# working.net
KiCad netlist of a schematic drawn in EAGLE
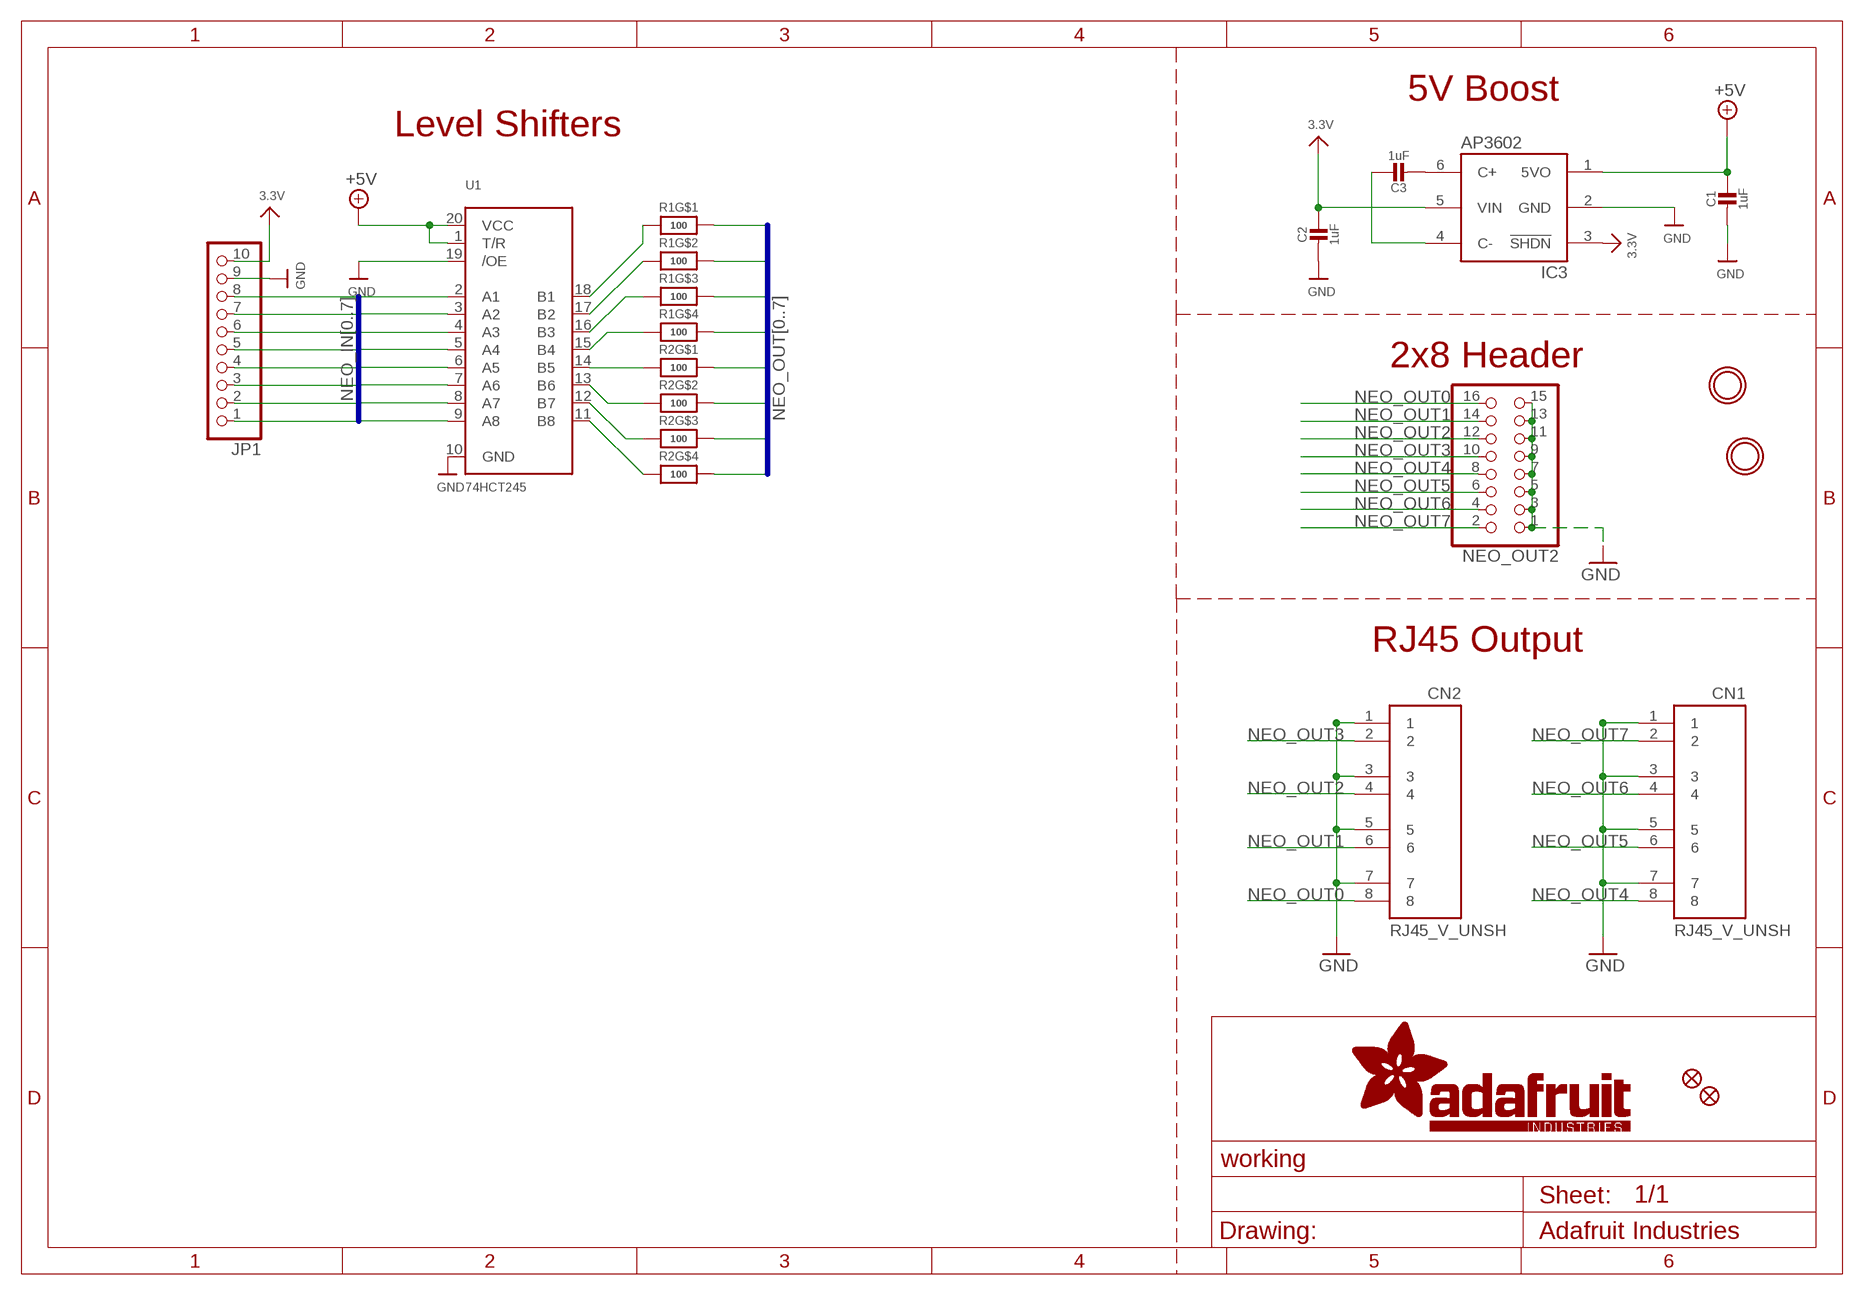
[diagram p0: schematic, sheet 1]

(export (version "E")
  (design (tool "Eeschema 10.0.6"))
  (components
    (comp (ref "C1")
      (value "1uF")
      (footprint "eagle-import:0603-NO")
      (libsource (lib "eagle-import") (part "CAP_CERAMIC0603_NO"))
    )
    (comp (ref "C2")
      (value "1uF")
      (footprint "eagle-import:0603-NO")
      (libsource (lib "eagle-import") (part "CAP_CERAMIC0603_NO"))
    )
    (comp (ref "C3")
      (value "1uF")
      (footprint "eagle-import:0603-NO")
      (libsource (lib "eagle-import") (part "CAP_CERAMIC0603_NO"))
    )
    (comp (ref "CN1")
      (value "RJ45_V_UNSH")
      (footprint "eagle-import:RJ45_VERTICAL_UNSHIELDED")
      (libsource (lib "eagle-import") (part "RJ45_V_UNSH"))
    )
    (comp (ref "CN2")
      (value "RJ45_V_UNSH")
      (footprint "eagle-import:RJ45_VERTICAL_UNSHIELDED")
      (libsource (lib "eagle-import") (part "RJ45_V_UNSH"))
    )
    (comp (ref "FID1")
      (value "FIDUCIAL_1MM")
      (footprint "eagle-import:FIDUCIAL_1MM")
      (libsource (lib "eagle-import") (part "FIDUCIAL_1MM"))
    )
    (comp (ref "FID2")
      (value "FIDUCIAL_1MM")
      (footprint "eagle-import:FIDUCIAL_1MM")
      (libsource (lib "eagle-import") (part "FIDUCIAL_1MM"))
    )
    (comp (ref "IC3")
      (value "AP3602")
      (footprint "eagle-import:SOT23-6")
      (libsource (lib "eagle-import") (part "AP3602"))
    )
    (comp (ref "JP1")
      (value "HEADER-1X1070MIL")
      (footprint "eagle-import:1X10_ROUND70")
      (libsource (lib "eagle-import") (part "HEADER-1X1070MIL"))
    )
    (comp (ref "NEO_OUT2")
      (value "HEADER-2X8")
      (footprint "eagle-import:2X08")
      (libsource (lib "eagle-import") (part "HEADER-2X8"))
    )
    (comp (ref "R1")
      (value "100")
      (footprint "eagle-import:RESPACK_4X0603")
      (libsource (lib "eagle-import") (part "RESISTOR_4PACK"))
    )
    (comp (ref "R2")
      (value "100")
      (footprint "eagle-import:RESPACK_4X0603")
      (libsource (lib "eagle-import") (part "RESISTOR_4PACK"))
    )
    (comp (ref "U$3")
      (value "MOUNTINGHOLE2.5")
      (footprint "eagle-import:MOUNTINGHOLE_2.5_PLATED")
      (libsource (lib "eagle-import") (part "MOUNTINGHOLE2.5"))
    )
    (comp (ref "U$7")
      (value "MOUNTINGHOLE2.5")
      (footprint "eagle-import:MOUNTINGHOLE_2.5_PLATED")
      (libsource (lib "eagle-import") (part "MOUNTINGHOLE2.5"))
    )
    (comp (ref "U1")
      (value "74HCT245")
      (footprint "eagle-import:TSSOP20")
      (libsource (lib "eagle-import") (part "74LCX245"))
    )
  )
  (nets
    (net (code "1") (name "+5V") (class "Default")
      (node (ref "C1") (pin "1") (pinfunction "1_1") (pintype "passive"))
      (node (ref "IC3") (pin "1") (pinfunction "5VO_1") (pintype "power_in"))
      (node (ref "U1") (pin "1") (pinfunction "T/R_1") (pintype "bidirectional"))
      (node (ref "U1") (pin "20") (pinfunction "VCC_20") (pintype "bidirectional"))
    )
    (net (code "2") (name "/NEO_IN0") (class "Default")
      (node (ref "JP1") (pin "8") (pinfunction "8_8") (pintype "passive"))
      (node (ref "U1") (pin "2") (pinfunction "A1_2") (pintype "bidirectional"))
    )
    (net (code "3") (name "/NEO_IN1") (class "Default")
      (node (ref "JP1") (pin "7") (pinfunction "7_7") (pintype "passive"))
      (node (ref "U1") (pin "3") (pinfunction "A2_3") (pintype "bidirectional"))
    )
    (net (code "4") (name "/NEO_IN2") (class "Default")
      (node (ref "JP1") (pin "6") (pinfunction "6_6") (pintype "passive"))
      (node (ref "U1") (pin "4") (pinfunction "A3_4") (pintype "bidirectional"))
    )
    (net (code "5") (name "/NEO_IN3") (class "Default")
      (node (ref "JP1") (pin "5") (pinfunction "5_5") (pintype "passive"))
      (node (ref "U1") (pin "5") (pinfunction "A4_5") (pintype "bidirectional"))
    )
    (net (code "6") (name "/NEO_IN4") (class "Default")
      (node (ref "JP1") (pin "4") (pinfunction "4_4") (pintype "passive"))
      (node (ref "U1") (pin "6") (pinfunction "A5_6") (pintype "bidirectional"))
    )
    (net (code "7") (name "/NEO_IN5") (class "Default")
      (node (ref "JP1") (pin "3") (pinfunction "3_3") (pintype "passive"))
      (node (ref "U1") (pin "7") (pinfunction "A6_7") (pintype "bidirectional"))
    )
    (net (code "8") (name "/NEO_IN6") (class "Default")
      (node (ref "JP1") (pin "2") (pinfunction "2_2") (pintype "passive"))
      (node (ref "U1") (pin "8") (pinfunction "A7_8") (pintype "bidirectional"))
    )
    (net (code "9") (name "/NEO_IN7") (class "Default")
      (node (ref "JP1") (pin "1") (pinfunction "1_1") (pintype "passive"))
      (node (ref "U1") (pin "9") (pinfunction "A8_9") (pintype "bidirectional"))
    )
    (net (code "10") (name "/NEO_OUT0") (class "Default")
      (node (ref "CN2") (pin "8") (pinfunction "8_8") (pintype "bidirectional"))
      (node (ref "NEO_OUT2") (pin "16") (pinfunction "16_16") (pintype "passive"))
      (node (ref "R1") (pin "8") (pinfunction "2_8") (pintype "passive"))
    )
    (net (code "11") (name "/NEO_OUT1") (class "Default")
      (node (ref "CN2") (pin "6") (pinfunction "6_6") (pintype "bidirectional"))
      (node (ref "NEO_OUT2") (pin "14") (pinfunction "14_14") (pintype "passive"))
      (node (ref "R1") (pin "7") (pinfunction "2_7") (pintype "passive"))
    )
    (net (code "12") (name "/NEO_OUT2") (class "Default")
      (node (ref "CN2") (pin "4") (pinfunction "4_4") (pintype "bidirectional"))
      (node (ref "NEO_OUT2") (pin "12") (pinfunction "12_12") (pintype "passive"))
      (node (ref "R1") (pin "6") (pinfunction "2_6") (pintype "passive"))
    )
    (net (code "13") (name "/NEO_OUT3") (class "Default")
      (node (ref "CN2") (pin "2") (pinfunction "2_2") (pintype "bidirectional"))
      (node (ref "NEO_OUT2") (pin "10") (pinfunction "10_10") (pintype "passive"))
      (node (ref "R1") (pin "5") (pinfunction "2_5") (pintype "passive"))
    )
    (net (code "14") (name "/NEO_OUT4") (class "Default")
      (node (ref "CN1") (pin "8") (pinfunction "8_8") (pintype "bidirectional"))
      (node (ref "NEO_OUT2") (pin "8") (pinfunction "8_8") (pintype "passive"))
      (node (ref "R2") (pin "8") (pinfunction "2_8") (pintype "passive"))
    )
    (net (code "15") (name "/NEO_OUT5") (class "Default")
      (node (ref "CN1") (pin "6") (pinfunction "6_6") (pintype "bidirectional"))
      (node (ref "NEO_OUT2") (pin "6") (pinfunction "6_6") (pintype "passive"))
      (node (ref "R2") (pin "7") (pinfunction "2_7") (pintype "passive"))
    )
    (net (code "16") (name "/NEO_OUT6") (class "Default")
      (node (ref "CN1") (pin "4") (pinfunction "4_4") (pintype "bidirectional"))
      (node (ref "NEO_OUT2") (pin "4") (pinfunction "4_4") (pintype "passive"))
      (node (ref "R2") (pin "6") (pinfunction "2_6") (pintype "passive"))
    )
    (net (code "17") (name "/NEO_OUT7") (class "Default")
      (node (ref "CN1") (pin "2") (pinfunction "2_2") (pintype "bidirectional"))
      (node (ref "NEO_OUT2") (pin "2") (pinfunction "2_2") (pintype "passive"))
      (node (ref "R2") (pin "5") (pinfunction "2_5") (pintype "passive"))
    )
    (net (code "19") (name "3.3V") (class "Default")
      (node (ref "C2") (pin "1") (pinfunction "1_1") (pintype "passive"))
      (node (ref "IC3") (pin "3") (pinfunction "~{SHDN}_3") (pintype "input"))
      (node (ref "IC3") (pin "5") (pinfunction "VIN_5") (pintype "power_in"))
      (node (ref "JP1") (pin "10") (pinfunction "10_10") (pintype "passive"))
    )
    (net (code "20") (name "GND") (class "Default")
      (node (ref "C1") (pin "2") (pinfunction "2_2") (pintype "passive"))
      (node (ref "C2") (pin "2") (pinfunction "2_2") (pintype "passive"))
      (node (ref "CN1") (pin "1") (pinfunction "1_1") (pintype "bidirectional"))
      (node (ref "CN1") (pin "3") (pinfunction "3_3") (pintype "bidirectional"))
      (node (ref "CN1") (pin "5") (pinfunction "5_5") (pintype "bidirectional"))
      (node (ref "CN1") (pin "7") (pinfunction "7_7") (pintype "bidirectional"))
      (node (ref "CN2") (pin "1") (pinfunction "1_1") (pintype "bidirectional"))
      (node (ref "CN2") (pin "3") (pinfunction "3_3") (pintype "bidirectional"))
      (node (ref "CN2") (pin "5") (pinfunction "5_5") (pintype "bidirectional"))
      (node (ref "CN2") (pin "7") (pinfunction "7_7") (pintype "bidirectional"))
      (node (ref "IC3") (pin "2") (pinfunction "GND_2") (pintype "power_in"))
      (node (ref "JP1") (pin "9") (pinfunction "9_9") (pintype "passive"))
      (node (ref "NEO_OUT2") (pin "1") (pinfunction "1_1") (pintype "passive"))
      (node (ref "NEO_OUT2") (pin "11") (pinfunction "11_11") (pintype "passive"))
      (node (ref "NEO_OUT2") (pin "13") (pinfunction "13_13") (pintype "passive"))
      (node (ref "NEO_OUT2") (pin "15") (pinfunction "15_15") (pintype "passive"))
      (node (ref "NEO_OUT2") (pin "3") (pinfunction "3_3") (pintype "passive"))
      (node (ref "NEO_OUT2") (pin "5") (pinfunction "5_5") (pintype "passive"))
      (node (ref "NEO_OUT2") (pin "7") (pinfunction "7_7") (pintype "passive"))
      (node (ref "NEO_OUT2") (pin "9") (pinfunction "9_9") (pintype "passive"))
      (node (ref "U1") (pin "10") (pinfunction "GND_10") (pintype "bidirectional"))
      (node (ref "U1") (pin "19") (pinfunction "/OE_19") (pintype "bidirectional"))
    )
    (net (code "21") (name "Net-(IC3-C+)") (class "Default")
      (node (ref "C3") (pin "2") (pinfunction "2_2") (pintype "passive"))
      (node (ref "IC3") (pin "6") (pinfunction "C+_6") (pintype "bidirectional"))
    )
    (net (code "22") (name "Net-(IC3-C-)") (class "Default")
      (node (ref "C3") (pin "1") (pinfunction "1_1") (pintype "passive"))
      (node (ref "IC3") (pin "4") (pinfunction "C-_4") (pintype "bidirectional"))
    )
    (net (code "23") (name "Net-(R1B-1)") (class "Default")
      (node (ref "R1") (pin "2") (pinfunction "1_2") (pintype "passive"))
      (node (ref "U1") (pin "17") (pinfunction "B2_17") (pintype "bidirectional"))
    )
    (net (code "24") (name "Net-(R1C-1)") (class "Default")
      (node (ref "R1") (pin "3") (pinfunction "1_3") (pintype "passive"))
      (node (ref "U1") (pin "16") (pinfunction "B3_16") (pintype "bidirectional"))
    )
    (net (code "25") (name "Net-(R1D-1)") (class "Default")
      (node (ref "R1") (pin "4") (pinfunction "1_4") (pintype "passive"))
      (node (ref "U1") (pin "15") (pinfunction "B4_15") (pintype "bidirectional"))
    )
    (net (code "26") (name "Net-(R2B-1)") (class "Default")
      (node (ref "R2") (pin "2") (pinfunction "1_2") (pintype "passive"))
      (node (ref "U1") (pin "13") (pinfunction "B6_13") (pintype "bidirectional"))
    )
    (net (code "27") (name "Net-(R2C-1)") (class "Default")
      (node (ref "R2") (pin "3") (pinfunction "1_3") (pintype "passive"))
      (node (ref "U1") (pin "12") (pinfunction "B7_12") (pintype "bidirectional"))
    )
    (net (code "28") (name "Net-(R2D-1)") (class "Default")
      (node (ref "R2") (pin "4") (pinfunction "1_4") (pintype "passive"))
      (node (ref "U1") (pin "11") (pinfunction "B8_11") (pintype "bidirectional"))
    )
    (net (code "29") (name "Net-(U1-B1)") (class "Default")
      (node (ref "R1") (pin "1") (pinfunction "1_1") (pintype "passive"))
      (node (ref "U1") (pin "18") (pinfunction "B1_18") (pintype "bidirectional"))
    )
    (net (code "30") (name "Net-(U1-B5)") (class "Default")
      (node (ref "R2") (pin "1") (pinfunction "1_1") (pintype "passive"))
      (node (ref "U1") (pin "14") (pinfunction "B5_14") (pintype "bidirectional"))
    )
  )
)
